# can-universalmodul_1_0.net
KiCad netlist of a schematic drawn in EAGLE
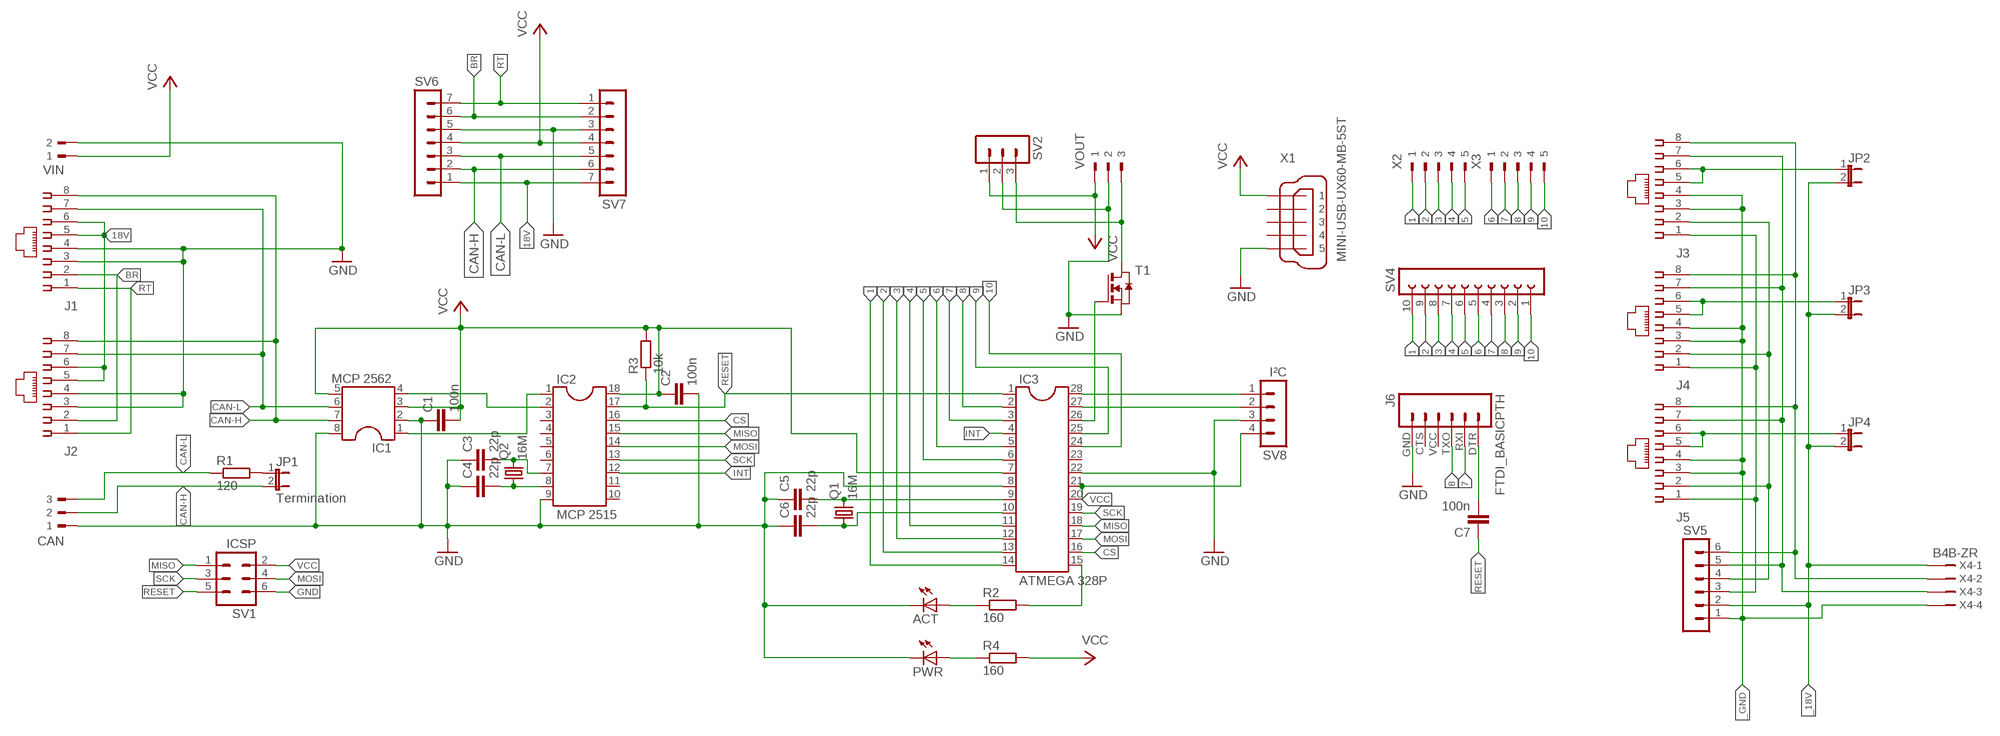
[diagram p0: schematic, sheet 1]

(export (version "E")
  (design (tool "Eeschema 10.0.6"))
  (components
    (comp (ref "ACT")
      (value "LEDCHIP-LED0805")
      (footprint "eagle-import:CHIP-LED0805")
      (libsource (lib "eagle-import") (part "LEDCHIP-LED0805"))
    )
    (comp (ref "C1")
      (value "100n")
      (footprint "eagle-import:C0805K")
      (libsource (lib "eagle-import") (part "C-EUC0805K"))
    )
    (comp (ref "C2")
      (value "100n")
      (footprint "eagle-import:C0805K")
      (libsource (lib "eagle-import") (part "C-EUC0805K"))
    )
    (comp (ref "C3")
      (value "22p")
      (footprint "eagle-import:C0805K")
      (libsource (lib "eagle-import") (part "C-EUC0805K"))
    )
    (comp (ref "C4")
      (value "22p")
      (footprint "eagle-import:C0805K")
      (libsource (lib "eagle-import") (part "C-EUC0805K"))
    )
    (comp (ref "C5")
      (value "22p")
      (footprint "eagle-import:C0805K")
      (libsource (lib "eagle-import") (part "C-EUC0805K"))
    )
    (comp (ref "C6")
      (value "22p")
      (footprint "eagle-import:C0805K")
      (libsource (lib "eagle-import") (part "C-EUC0805K"))
    )
    (comp (ref "C7")
      (value "100n")
      (footprint "eagle-import:C0805K")
      (libsource (lib "eagle-import") (part "C-EUC0805K"))
    )
    (comp (ref "CAN")
      (value "90-3")
      (footprint "eagle-import:90-3")
      (libsource (lib "eagle-import") (part "90-3"))
    )
    (comp (ref "IC1")
      (value "MCP 2562")
      (footprint "eagle-import:SOCKET-08")
      (libsource (lib "eagle-import") (part "DIL8S"))
    )
    (comp (ref "IC2")
      (value "MCP 2515")
      (footprint "eagle-import:SOCKET-18")
      (libsource (lib "eagle-import") (part "DIL18S"))
    )
    (comp (ref "IC3")
      (value "ATMEGA 328P")
      (footprint "eagle-import:DIL28-3")
      (libsource (lib "eagle-import") (part "DIL28-3"))
    )
    (comp (ref "J1")
      (value "215877-7")
      (footprint "eagle-import:215877-7")
      (libsource (lib "eagle-import") (part "215877-7"))
    )
    (comp (ref "J2")
      (value "215877-7")
      (footprint "eagle-import:215877-7")
      (libsource (lib "eagle-import") (part "215877-7"))
    )
    (comp (ref "J3")
      (value "215877-7")
      (footprint "eagle-import:215877-7")
      (libsource (lib "eagle-import") (part "215877-7"))
    )
    (comp (ref "J4")
      (value "215877-7")
      (footprint "eagle-import:215877-7")
      (libsource (lib "eagle-import") (part "215877-7"))
    )
    (comp (ref "J5")
      (value "215877-7")
      (footprint "eagle-import:215877-7")
      (libsource (lib "eagle-import") (part "215877-7"))
    )
    (comp (ref "J6")
      (value "FTDI_BASICPTH")
      (footprint "eagle-import:FTDI_BASIC")
      (libsource (lib "eagle-import") (part "FTDI_BASICPTH"))
    )
    (comp (ref "JP1")
      (value "Termination")
      (footprint "eagle-import:JP1")
      (libsource (lib "eagle-import") (part "JP1E"))
    )
    (comp (ref "JP2")
      (value "JP1E")
      (footprint "eagle-import:JP1")
      (libsource (lib "eagle-import") (part "JP1E"))
    )
    (comp (ref "JP3")
      (value "JP1E")
      (footprint "eagle-import:JP1")
      (libsource (lib "eagle-import") (part "JP1E"))
    )
    (comp (ref "JP4")
      (value "JP1E")
      (footprint "eagle-import:JP1")
      (libsource (lib "eagle-import") (part "JP1E"))
    )
    (comp (ref "PWR")
      (value "LEDCHIP-LED0805")
      (footprint "eagle-import:CHIP-LED0805")
      (libsource (lib "eagle-import") (part "LEDCHIP-LED0805"))
    )
    (comp (ref "Q1")
      (value "16M")
      (footprint "eagle-import:CSM-7X-DU")
      (libsource (lib "eagle-import") (part "CSM-7X-DU"))
    )
    (comp (ref "Q2")
      (value "16M")
      (footprint "eagle-import:CSM-7X-DU")
      (libsource (lib "eagle-import") (part "CSM-7X-DU"))
    )
    (comp (ref "R1")
      (value "120")
      (footprint "eagle-import:R0805")
      (libsource (lib "eagle-import") (part "R-EU_R0805"))
    )
    (comp (ref "R2")
      (value "160")
      (footprint "eagle-import:R0805")
      (libsource (lib "eagle-import") (part "R-EU_R0805"))
    )
    (comp (ref "R3")
      (value "10k")
      (footprint "eagle-import:R0805")
      (libsource (lib "eagle-import") (part "R-EU_R0805"))
    )
    (comp (ref "R4")
      (value "160")
      (footprint "eagle-import:R0805")
      (libsource (lib "eagle-import") (part "R-EU_R0805"))
    )
    (comp (ref "SV1")
      (value "ICSP")
      (footprint "eagle-import:MA03-2")
      (libsource (lib "eagle-import") (part "MA03-2"))
    )
    (comp (ref "SV2")
      (value "MA03-1")
      (footprint "eagle-import:MA03-1")
      (libsource (lib "eagle-import") (part "MA03-1"))
    )
    (comp (ref "SV4")
      (value "FE10W")
      (footprint "eagle-import:FE10W")
      (libsource (lib "eagle-import") (part "FE10W"))
    )
    (comp (ref "SV5")
      (value "MA06-1")
      (footprint "eagle-import:MA06-1")
      (libsource (lib "eagle-import") (part "MA06-1"))
    )
    (comp (ref "SV6")
      (value "MA07-1")
      (footprint "eagle-import:MA07-1")
      (libsource (lib "eagle-import") (part "MA07-1"))
    )
    (comp (ref "SV7")
      (value "MA07-1")
      (footprint "eagle-import:MA07-1")
      (libsource (lib "eagle-import") (part "MA07-1"))
    )
    (comp (ref "SV8")
      (value "I²C")
      (footprint "eagle-import:MA04-1")
      (libsource (lib "eagle-import") (part "MA04-1"))
    )
    (comp (ref "T1")
      (value "NMOSSOT23")
      (footprint "eagle-import:SOT-23")
      (libsource (lib "eagle-import") (part "NMOSSOT23"))
    )
    (comp (ref "VIN")
      (value "90-2")
      (footprint "eagle-import:90-2")
      (libsource (lib "eagle-import") (part "90-2"))
    )
    (comp (ref "VOUT")
      (value "90-3")
      (footprint "eagle-import:90-3")
      (libsource (lib "eagle-import") (part "90-3"))
    )
    (comp (ref "X1")
      (value "MINI-USB-UX60-MB-5ST")
      (footprint "eagle-import:UX60-MB-5ST")
      (libsource (lib "eagle-import") (part "MINI-USB-UX60-MB-5ST"))
    )
    (comp (ref "X2")
      (value "90-5")
      (footprint "eagle-import:90-5")
      (libsource (lib "eagle-import") (part "90-5"))
    )
    (comp (ref "X3")
      (value "90-5")
      (footprint "eagle-import:90-5")
      (libsource (lib "eagle-import") (part "90-5"))
    )
    (comp (ref "X4")
      (value "B4B-ZR")
      (footprint "eagle-import:B4B-ZR")
      (fields (field (name "MF") "FARNELL") (field (name "MPN") "B4B-ZR(LF)(SN)"))
      (libsource (lib "eagle-import") (part "?4B-ZRB"))
    )
  )
  (nets
    (net (code "1") (name "1") (class "Default")
      (node (ref "IC3") (pin "14") (pinfunction "14_14") (pintype "passive"))
      (node (ref "SV4") (pin "10") (pinfunction "10_10") (pintype "passive"))
      (node (ref "X2") (pin "1") (pinfunction "1_1") (pintype "passive"))
    )
    (net (code "2") (name "2") (class "Default")
      (node (ref "IC3") (pin "13") (pinfunction "13_13") (pintype "passive"))
      (node (ref "SV4") (pin "9") (pinfunction "9_9") (pintype "passive"))
      (node (ref "X2") (pin "2") (pinfunction "2_2") (pintype "passive"))
    )
    (net (code "3") (name "3") (class "Default")
      (node (ref "IC3") (pin "12") (pinfunction "12_12") (pintype "passive"))
      (node (ref "SV4") (pin "8") (pinfunction "8_8") (pintype "passive"))
      (node (ref "X2") (pin "3") (pinfunction "3_3") (pintype "passive"))
    )
    (net (code "4") (name "4") (class "Default")
      (node (ref "IC3") (pin "11") (pinfunction "11_11") (pintype "passive"))
      (node (ref "SV4") (pin "7") (pinfunction "7_7") (pintype "passive"))
      (node (ref "X2") (pin "4") (pinfunction "4_4") (pintype "passive"))
    )
    (net (code "5") (name "5") (class "Default")
      (node (ref "IC3") (pin "6") (pinfunction "6_6") (pintype "passive"))
      (node (ref "SV4") (pin "6") (pinfunction "6_6") (pintype "passive"))
      (node (ref "X2") (pin "5") (pinfunction "5_5") (pintype "passive"))
    )
    (net (code "6") (name "6") (class "Default")
      (node (ref "IC3") (pin "5") (pinfunction "5_5") (pintype "passive"))
      (node (ref "SV4") (pin "5") (pinfunction "5_5") (pintype "passive"))
      (node (ref "X3") (pin "1") (pinfunction "1_1") (pintype "passive"))
    )
    (net (code "7") (name "7") (class "Default")
      (node (ref "IC3") (pin "3") (pinfunction "3_3") (pintype "passive"))
      (node (ref "J6") (pin "RXI") (pinfunction "2_RXI") (pintype "passive"))
      (node (ref "SV4") (pin "4") (pinfunction "4_4") (pintype "passive"))
      (node (ref "X3") (pin "2") (pinfunction "2_2") (pintype "passive"))
    )
    (net (code "8") (name "8") (class "Default")
      (node (ref "IC3") (pin "2") (pinfunction "2_2") (pintype "passive"))
      (node (ref "J6") (pin "TXO") (pinfunction "3_TXO") (pintype "passive"))
      (node (ref "SV4") (pin "3") (pinfunction "3_3") (pintype "passive"))
      (node (ref "X3") (pin "3") (pinfunction "3_3") (pintype "passive"))
    )
    (net (code "9") (name "9") (class "Default")
      (node (ref "IC3") (pin "25") (pinfunction "25_25") (pintype "passive"))
      (node (ref "SV4") (pin "2") (pinfunction "2_2") (pintype "passive"))
      (node (ref "X3") (pin "4") (pinfunction "4_4") (pintype "passive"))
    )
    (net (code "10") (name "10") (class "Default")
      (node (ref "IC3") (pin "24") (pinfunction "24_24") (pintype "passive"))
      (node (ref "SV4") (pin "1") (pinfunction "1_1") (pintype "passive"))
      (node (ref "X3") (pin "5") (pinfunction "5_5") (pintype "passive"))
    )
    (net (code "11") (name "18V") (class "Default")
      (node (ref "J1") (pin "5") (pinfunction "5_5") (pintype "passive"))
      (node (ref "J1") (pin "6") (pinfunction "6_6") (pintype "passive"))
      (node (ref "J2") (pin "5") (pinfunction "5_5") (pintype "passive"))
      (node (ref "J2") (pin "6") (pinfunction "6_6") (pintype "passive"))
      (node (ref "SV6") (pin "1") (pinfunction "1_1") (pintype "passive"))
      (node (ref "SV7") (pin "7") (pinfunction "7_7") (pintype "passive"))
    )
    (net (code "12") (name "BR") (class "Default")
      (node (ref "J1") (pin "2") (pinfunction "2_2") (pintype "passive"))
      (node (ref "J2") (pin "2") (pinfunction "2_2") (pintype "passive"))
      (node (ref "SV6") (pin "6") (pinfunction "6_6") (pintype "passive"))
      (node (ref "SV7") (pin "2") (pinfunction "2_2") (pintype "passive"))
    )
    (net (code "13") (name "CAN-H") (class "Default")
      (node (ref "CAN") (pin "2") (pinfunction "2_2") (pintype "passive"))
      (node (ref "IC1") (pin "7") (pinfunction "7_7") (pintype "passive"))
      (node (ref "J1") (pin "8") (pinfunction "8_8") (pintype "passive"))
      (node (ref "J2") (pin "8") (pinfunction "8_8") (pintype "passive"))
      (node (ref "JP1") (pin "2") (pinfunction "2_2") (pintype "passive"))
      (node (ref "SV6") (pin "2") (pinfunction "2_2") (pintype "passive"))
      (node (ref "SV7") (pin "6") (pinfunction "6_6") (pintype "passive"))
    )
    (net (code "14") (name "CAN-L") (class "Default")
      (node (ref "CAN") (pin "3") (pinfunction "3_3") (pintype "passive"))
      (node (ref "IC1") (pin "6") (pinfunction "6_6") (pintype "passive"))
      (node (ref "J1") (pin "7") (pinfunction "7_7") (pintype "passive"))
      (node (ref "J2") (pin "7") (pinfunction "7_7") (pintype "passive"))
      (node (ref "R1") (pin "1") (pinfunction "1_1") (pintype "passive"))
      (node (ref "SV6") (pin "3") (pinfunction "3_3") (pintype "passive"))
      (node (ref "SV7") (pin "5") (pinfunction "5_5") (pintype "passive"))
    )
    (net (code "15") (name "CS") (class "Default")
      (node (ref "IC2") (pin "16") (pinfunction "16_16") (pintype "passive"))
      (node (ref "IC3") (pin "16") (pinfunction "16_16") (pintype "passive"))
    )
    (net (code "16") (name "GND") (class "Default")
      (node (ref "ACT") (pin "C") (pinfunction "C_C") (pintype "passive"))
      (node (ref "C1") (pin "1") (pinfunction "1_1") (pintype "passive"))
      (node (ref "C2") (pin "2") (pinfunction "2_2") (pintype "passive"))
      (node (ref "C3") (pin "1") (pinfunction "1_1") (pintype "passive"))
      (node (ref "C4") (pin "1") (pinfunction "1_1") (pintype "passive"))
      (node (ref "C5") (pin "1") (pinfunction "1_1") (pintype "passive"))
      (node (ref "C6") (pin "1") (pinfunction "1_1") (pintype "passive"))
      (node (ref "CAN") (pin "1") (pinfunction "1_1") (pintype "passive"))
      (node (ref "IC1") (pin "2") (pinfunction "2_2") (pintype "passive"))
      (node (ref "IC1") (pin "8") (pinfunction "8_8") (pintype "passive"))
      (node (ref "IC2") (pin "9") (pinfunction "9_9") (pintype "passive"))
      (node (ref "IC3") (pin "22") (pinfunction "22_22") (pintype "passive"))
      (node (ref "IC3") (pin "8") (pinfunction "8_8") (pintype "passive"))
      (node (ref "J1") (pin "3") (pinfunction "3_3") (pintype "passive"))
      (node (ref "J1") (pin "4") (pinfunction "4_4") (pintype "passive"))
      (node (ref "J2") (pin "3") (pinfunction "3_3") (pintype "passive"))
      (node (ref "J2") (pin "4") (pinfunction "4_4") (pintype "passive"))
      (node (ref "J6") (pin "GND") (pinfunction "6_GND") (pintype "passive"))
      (node (ref "PWR") (pin "C") (pinfunction "C_C") (pintype "passive"))
      (node (ref "SV1") (pin "6") (pinfunction "6_6") (pintype "passive"))
      (node (ref "SV2") (pin "2") (pinfunction "2_2") (pintype "passive"))
      (node (ref "SV6") (pin "5") (pinfunction "5_5") (pintype "passive"))
      (node (ref "SV7") (pin "3") (pinfunction "3_3") (pintype "passive"))
      (node (ref "SV8") (pin "3") (pinfunction "3_3") (pintype "passive"))
      (node (ref "T1") (pin "2") (pinfunction "S_2") (pintype "passive"))
      (node (ref "VIN") (pin "2") (pinfunction "2_2") (pintype "passive"))
      (node (ref "VOUT") (pin "2") (pinfunction "2_2") (pintype "passive"))
      (node (ref "X1") (pin "5") (pinfunction "5_5") (pintype "input"))
    )
    (net (code "17") (name "INT") (class "Default")
      (node (ref "IC2") (pin "12") (pinfunction "12_12") (pintype "passive"))
      (node (ref "IC3") (pin "4") (pinfunction "4_4") (pintype "passive"))
    )
    (net (code "18") (name "MISO") (class "Default")
      (node (ref "IC2") (pin "15") (pinfunction "15_15") (pintype "passive"))
      (node (ref "IC3") (pin "18") (pinfunction "18_18") (pintype "passive"))
      (node (ref "SV1") (pin "1") (pinfunction "1_1") (pintype "passive"))
    )
    (net (code "19") (name "MOSI") (class "Default")
      (node (ref "IC2") (pin "14") (pinfunction "14_14") (pintype "passive"))
      (node (ref "IC3") (pin "17") (pinfunction "17_17") (pintype "passive"))
      (node (ref "SV1") (pin "4") (pinfunction "4_4") (pintype "passive"))
    )
    (net (code "20") (name "Net-(ACT-PadA)") (class "Default")
      (node (ref "ACT") (pin "A") (pinfunction "A_A") (pintype "passive"))
      (node (ref "R2") (pin "1") (pinfunction "1_1") (pintype "passive"))
    )
    (net (code "21") (name "Net-(C3-Pad2)") (class "Default")
      (node (ref "C3") (pin "2") (pinfunction "2_2") (pintype "passive"))
      (node (ref "IC2") (pin "7") (pinfunction "7_7") (pintype "passive"))
      (node (ref "Q2") (pin "2") (pinfunction "2_2") (pintype "passive"))
    )
    (net (code "22") (name "Net-(C4-Pad2)") (class "Default")
      (node (ref "C4") (pin "2") (pinfunction "2_2") (pintype "passive"))
      (node (ref "IC2") (pin "8") (pinfunction "8_8") (pintype "passive"))
      (node (ref "Q2") (pin "1") (pinfunction "1_1") (pintype "passive"))
    )
    (net (code "23") (name "Net-(C5-Pad2)") (class "Default")
      (node (ref "C5") (pin "2") (pinfunction "2_2") (pintype "passive"))
      (node (ref "IC3") (pin "9") (pinfunction "9_9") (pintype "passive"))
      (node (ref "Q1") (pin "2") (pinfunction "2_2") (pintype "passive"))
    )
    (net (code "24") (name "Net-(C6-Pad2)") (class "Default")
      (node (ref "C6") (pin "2") (pinfunction "2_2") (pintype "passive"))
      (node (ref "IC3") (pin "10") (pinfunction "10_10") (pintype "passive"))
      (node (ref "Q1") (pin "1") (pinfunction "1_1") (pintype "passive"))
    )
    (net (code "25") (name "Net-(IC1-Pad1)") (class "Default")
      (node (ref "IC1") (pin "1") (pinfunction "1_1") (pintype "passive"))
      (node (ref "IC2") (pin "1") (pinfunction "1_1") (pintype "passive"))
    )
    (net (code "26") (name "Net-(IC1-Pad4)") (class "Default")
      (node (ref "IC1") (pin "4") (pinfunction "4_4") (pintype "passive"))
      (node (ref "IC2") (pin "2") (pinfunction "2_2") (pintype "passive"))
    )
    (net (code "27") (name "Net-(IC3-Pad15)") (class "Default")
      (node (ref "IC3") (pin "15") (pinfunction "15_15") (pintype "passive"))
      (node (ref "R2") (pin "2") (pinfunction "2_2") (pintype "passive"))
    )
    (net (code "28") (name "Net-(IC3-Pad27)") (class "Default")
      (node (ref "IC3") (pin "27") (pinfunction "27_27") (pintype "passive"))
      (node (ref "SV8") (pin "2") (pinfunction "2_2") (pintype "passive"))
    )
    (net (code "29") (name "Net-(IC3-Pad28)") (class "Default")
      (node (ref "IC3") (pin "28") (pinfunction "28_28") (pintype "passive"))
      (node (ref "SV8") (pin "1") (pinfunction "1_1") (pintype "passive"))
    )
    (net (code "30") (name "Net-(J3-Pad1)") (class "Default")
      (node (ref "J3") (pin "1") (pinfunction "1_1") (pintype "passive"))
      (node (ref "J4") (pin "1") (pinfunction "1_1") (pintype "passive"))
      (node (ref "J5") (pin "1") (pinfunction "1_1") (pintype "passive"))
      (node (ref "SV5") (pin "3") (pinfunction "3_3") (pintype "passive"))
    )
    (net (code "31") (name "Net-(J3-Pad2)") (class "Default")
      (node (ref "J3") (pin "2") (pinfunction "2_2") (pintype "passive"))
      (node (ref "J4") (pin "2") (pinfunction "2_2") (pintype "passive"))
      (node (ref "J5") (pin "2") (pinfunction "2_2") (pintype "passive"))
      (node (ref "SV5") (pin "4") (pinfunction "4_4") (pintype "passive"))
    )
    (net (code "32") (name "Net-(J3-Pad5)") (class "Default")
      (node (ref "J3") (pin "5") (pinfunction "5_5") (pintype "passive"))
      (node (ref "J3") (pin "6") (pinfunction "6_6") (pintype "passive"))
      (node (ref "JP2") (pin "1") (pinfunction "1_1") (pintype "passive"))
    )
    (net (code "33") (name "Net-(J4-Pad5)") (class "Default")
      (node (ref "J4") (pin "5") (pinfunction "5_5") (pintype "passive"))
      (node (ref "J4") (pin "6") (pinfunction "6_6") (pintype "passive"))
      (node (ref "JP3") (pin "1") (pinfunction "1_1") (pintype "passive"))
    )
    (net (code "34") (name "Net-(J5-Pad5)") (class "Default")
      (node (ref "J5") (pin "5") (pinfunction "5_5") (pintype "passive"))
      (node (ref "J5") (pin "6") (pinfunction "6_6") (pintype "passive"))
      (node (ref "JP4") (pin "1") (pinfunction "1_1") (pintype "passive"))
    )
    (net (code "35") (name "Net-(J6-1)") (class "Default")
      (node (ref "C7") (pin "2") (pinfunction "2_2") (pintype "passive"))
      (node (ref "J6") (pin "DTR") (pinfunction "1_DTR") (pintype "passive"))
    )
    (net (code "36") (name "Net-(JP1-Pad1)") (class "Default")
      (node (ref "JP1") (pin "1") (pinfunction "1_1") (pintype "passive"))
      (node (ref "R1") (pin "2") (pinfunction "2_2") (pintype "passive"))
    )
    (net (code "37") (name "Net-(PWR-PadA)") (class "Default")
      (node (ref "PWR") (pin "A") (pinfunction "A_A") (pintype "passive"))
      (node (ref "R4") (pin "1") (pinfunction "1_1") (pintype "passive"))
    )
    (net (code "38") (name "Net-(T1-D)") (class "Default")
      (node (ref "SV2") (pin "3") (pinfunction "3_3") (pintype "passive"))
      (node (ref "T1") (pin "1") (pinfunction "D_1") (pintype "passive"))
      (node (ref "VOUT") (pin "3") (pinfunction "3_3") (pintype "passive"))
    )
    (net (code "39") (name "Net-(T1-G)") (class "Default")
      (node (ref "IC3") (pin "26") (pinfunction "26_26") (pintype "passive"))
      (node (ref "T1") (pin "3") (pinfunction "G_3") (pintype "passive"))
    )
    (net (code "40") (name "Net-(X4B-1)") (class "Default")
      (node (ref "J3") (pin "8") (pinfunction "8_8") (pintype "passive"))
      (node (ref "J4") (pin "8") (pinfunction "8_8") (pintype "passive"))
      (node (ref "J5") (pin "8") (pinfunction "8_8") (pintype "passive"))
      (node (ref "SV5") (pin "6") (pinfunction "6_6") (pintype "passive"))
      (node (ref "X4") (pin "2") (pinfunction "1_2") (pintype "passive"))
    )
    (net (code "41") (name "Net-(X4C-1)") (class "Default")
      (node (ref "J3") (pin "7") (pinfunction "7_7") (pintype "passive"))
      (node (ref "J4") (pin "7") (pinfunction "7_7") (pintype "passive"))
      (node (ref "J5") (pin "7") (pinfunction "7_7") (pintype "passive"))
      (node (ref "SV5") (pin "5") (pinfunction "5_5") (pintype "passive"))
      (node (ref "X4") (pin "3") (pinfunction "1_3") (pintype "passive"))
    )
    (net (code "42") (name "RESET") (class "Default")
      (node (ref "C7") (pin "1") (pinfunction "1_1") (pintype "passive"))
      (node (ref "IC2") (pin "17") (pinfunction "17_17") (pintype "passive"))
      (node (ref "IC3") (pin "1") (pinfunction "1_1") (pintype "passive"))
      (node (ref "R3") (pin "1") (pinfunction "1_1") (pintype "passive"))
      (node (ref "SV1") (pin "5") (pinfunction "5_5") (pintype "passive"))
    )
    (net (code "43") (name "RT") (class "Default")
      (node (ref "J1") (pin "1") (pinfunction "1_1") (pintype "passive"))
      (node (ref "J2") (pin "1") (pinfunction "1_1") (pintype "passive"))
      (node (ref "SV6") (pin "7") (pinfunction "7_7") (pintype "passive"))
      (node (ref "SV7") (pin "1") (pinfunction "1_1") (pintype "passive"))
    )
    (net (code "44") (name "SCK") (class "Default")
      (node (ref "IC2") (pin "13") (pinfunction "13_13") (pintype "passive"))
      (node (ref "IC3") (pin "19") (pinfunction "19_19") (pintype "passive"))
      (node (ref "SV1") (pin "3") (pinfunction "3_3") (pintype "passive"))
    )
    (net (code "45") (name "VCC") (class "Default")
      (node (ref "C1") (pin "2") (pinfunction "2_2") (pintype "passive"))
      (node (ref "C2") (pin "1") (pinfunction "1_1") (pintype "passive"))
      (node (ref "IC1") (pin "3") (pinfunction "3_3") (pintype "passive"))
      (node (ref "IC1") (pin "5") (pinfunction "5_5") (pintype "passive"))
      (node (ref "IC2") (pin "18") (pinfunction "18_18") (pintype "passive"))
      (node (ref "IC3") (pin "20") (pinfunction "20_20") (pintype "passive"))
      (node (ref "IC3") (pin "21") (pinfunction "21_21") (pintype "passive"))
      (node (ref "IC3") (pin "7") (pinfunction "7_7") (pintype "passive"))
      (node (ref "R3") (pin "2") (pinfunction "2_2") (pintype "passive"))
      (node (ref "R4") (pin "2") (pinfunction "2_2") (pintype "passive"))
      (node (ref "SV1") (pin "2") (pinfunction "2_2") (pintype "passive"))
      (node (ref "SV2") (pin "1") (pinfunction "1_1") (pintype "passive"))
      (node (ref "SV6") (pin "4") (pinfunction "4_4") (pintype "passive"))
      (node (ref "SV7") (pin "4") (pinfunction "4_4") (pintype "passive"))
      (node (ref "SV8") (pin "4") (pinfunction "4_4") (pintype "passive"))
      (node (ref "VIN") (pin "1") (pinfunction "1_1") (pintype "passive"))
      (node (ref "VOUT") (pin "1") (pinfunction "1_1") (pintype "passive"))
      (node (ref "X1") (pin "1") (pinfunction "1_1") (pintype "input"))
    )
    (net (code "46") (name "_18V") (class "Default")
      (node (ref "JP2") (pin "2") (pinfunction "2_2") (pintype "passive"))
      (node (ref "JP3") (pin "2") (pinfunction "2_2") (pintype "passive"))
      (node (ref "JP4") (pin "2") (pinfunction "2_2") (pintype "passive"))
      (node (ref "SV5") (pin "2") (pinfunction "2_2") (pintype "passive"))
      (node (ref "X4") (pin "1") (pinfunction "1_1") (pintype "passive"))
    )
    (net (code "47") (name "_GND") (class "Default")
      (node (ref "J3") (pin "3") (pinfunction "3_3") (pintype "passive"))
      (node (ref "J3") (pin "4") (pinfunction "4_4") (pintype "passive"))
      (node (ref "J4") (pin "3") (pinfunction "3_3") (pintype "passive"))
      (node (ref "J4") (pin "4") (pinfunction "4_4") (pintype "passive"))
      (node (ref "J5") (pin "3") (pinfunction "3_3") (pintype "passive"))
      (node (ref "J5") (pin "4") (pinfunction "4_4") (pintype "passive"))
      (node (ref "SV5") (pin "1") (pinfunction "1_1") (pintype "passive"))
      (node (ref "X4") (pin "4") (pinfunction "1_4") (pintype "passive"))
    )
    (net (code "48") (name "unconnected-(IC2-Pad3)") (class "Default")
      (node (ref "IC2") (pin "3") (pinfunction "3_3") (pintype "passive"))
    )
    (net (code "49") (name "unconnected-(IC2-Pad4)") (class "Default")
      (node (ref "IC2") (pin "4") (pinfunction "4_4") (pintype "passive"))
    )
    (net (code "50") (name "unconnected-(IC2-Pad5)") (class "Default")
      (node (ref "IC2") (pin "5") (pinfunction "5_5") (pintype "passive"))
    )
    (net (code "51") (name "unconnected-(IC2-Pad6)") (class "Default")
      (node (ref "IC2") (pin "6") (pinfunction "6_6") (pintype "passive"))
    )
    (net (code "52") (name "unconnected-(IC2-Pad10)") (class "Default")
      (node (ref "IC2") (pin "10") (pinfunction "10_10") (pintype "passive"))
    )
    (net (code "53") (name "unconnected-(IC2-Pad11)") (class "Default")
      (node (ref "IC2") (pin "11") (pinfunction "11_11") (pintype "passive"))
    )
    (net (code "54") (name "unconnected-(IC3-Pad23)") (class "Default")
      (node (ref "IC3") (pin "23") (pinfunction "23_23") (pintype "passive"))
    )
    (net (code "55") (name "unconnected-(J6-4-PadVCC)") (class "Default")
      (node (ref "J6") (pin "VCC") (pinfunction "4_VCC") (pintype "passive"))
    )
    (net (code "56") (name "unconnected-(J6-5-PadCTS)") (class "Default")
      (node (ref "J6") (pin "CTS") (pinfunction "5_CTS") (pintype "passive"))
    )
    (net (code "57") (name "unconnected-(X1-Pad2)") (class "Default")
      (node (ref "X1") (pin "2") (pinfunction "2_2") (pintype "input"))
    )
    (net (code "58") (name "unconnected-(X1-Pad3)") (class "Default")
      (node (ref "X1") (pin "3") (pinfunction "3_3") (pintype "input"))
    )
    (net (code "59") (name "unconnected-(X1-Pad4)") (class "Default")
      (node (ref "X1") (pin "4") (pinfunction "4_4") (pintype "input"))
    )
  )
)
